# MIDI_connector.net
KiCad netlist of a schematic drawn in Altium Designer
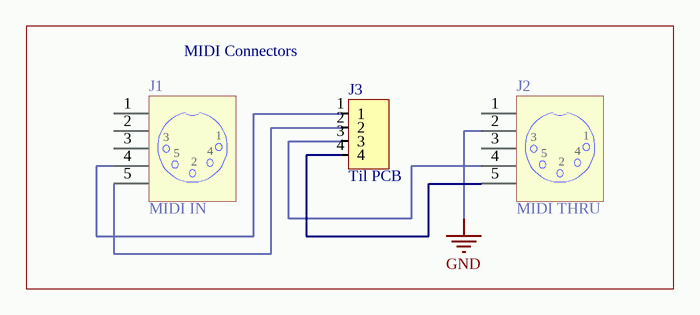
[diagram p0: MIDI_connector.SchDoc]

(export (version "E")
  (design (tool "Eeschema 10.0.6"))
  (components
    (comp (ref "J1")
      (value "MIDI IN")
      (footprint "KONV-KMFCDIN76005_V")
      (description "Socket, 5-way R/A DIN")
      (fields (field (name "MANUFACTURER") "Konvee Electronic") (field (name "PARTNUMBER") "KMFCDIN76005"))
      (libsource (lib "Altium Content Vault") (part "CMP-0406-00001-1"))
    )
    (comp (ref "J2")
      (value "MIDI THRU")
      (footprint "KONV-KMFCDIN76005_V")
      (description "Socket, 5-way R/A DIN")
      (fields (field (name "MANUFACTURER") "Konvee Electronic") (field (name "PARTNUMBER") "KMFCDIN76005"))
      (libsource (lib "Altium Content Vault") (part "CMP-0406-00001-1"))
    )
    (comp (ref "J3") (value "Til PCB") (footprint "JST 4pin") (libsource (lib "Schlib1") (part "JST 4pin")))
  )
  (nets
    (net (code "1") (name "GND") (class "Default")
      (node (ref "J2") (pin "2") (pinfunction "2_2") (pintype "passive"))
    )
    (net (code "2") (name "Net-(J1-Pad4)") (class "Default")
      (node (ref "J1") (pin "4") (pinfunction "4_4") (pintype "passive"))
      (node (ref "J3") (pin "1") (pinfunction "1_1") (pintype "passive"))
    )
    (net (code "3") (name "Net-(J1-Pad5)") (class "Default")
      (node (ref "J1") (pin "5") (pinfunction "5_5") (pintype "passive"))
      (node (ref "J3") (pin "2") (pinfunction "2_2") (pintype "passive"))
    )
    (net (code "4") (name "Net-(J2-Pad4)") (class "Default")
      (node (ref "J2") (pin "4") (pinfunction "4_4") (pintype "passive"))
      (node (ref "J3") (pin "3") (pinfunction "3_3") (pintype "passive"))
    )
    (net (code "5") (name "Net-(J2-Pad5)") (class "Default")
      (node (ref "J2") (pin "5") (pinfunction "5_5") (pintype "passive"))
      (node (ref "J3") (pin "4") (pinfunction "4_4") (pintype "passive"))
    )
    (net (code "6") (name "unconnected-(J1-Pad1)") (class "Default")
      (node (ref "J1") (pin "1") (pinfunction "1_1") (pintype "passive"))
    )
    (net (code "7") (name "unconnected-(J1-Pad2)") (class "Default")
      (node (ref "J1") (pin "2") (pinfunction "2_2") (pintype "passive"))
    )
    (net (code "8") (name "unconnected-(J1-Pad3)") (class "Default")
      (node (ref "J1") (pin "3") (pinfunction "3_3") (pintype "passive"))
    )
    (net (code "9") (name "unconnected-(J1-PadMH1)") (class "Default")
      (node (ref "J1") (pin "MH1") (pinfunction "MH1_MH1") (pintype "passive"))
    )
    (net (code "10") (name "unconnected-(J1-PadMH2)") (class "Default")
      (node (ref "J1") (pin "MH2") (pinfunction "MH2_MH2") (pintype "passive"))
    )
    (net (code "11") (name "unconnected-(J2-Pad1)") (class "Default")
      (node (ref "J2") (pin "1") (pinfunction "1_1") (pintype "passive"))
    )
    (net (code "12") (name "unconnected-(J2-Pad3)") (class "Default")
      (node (ref "J2") (pin "3") (pinfunction "3_3") (pintype "passive"))
    )
    (net (code "13") (name "unconnected-(J2-PadMH1)") (class "Default")
      (node (ref "J2") (pin "MH1") (pinfunction "MH1_MH1") (pintype "passive"))
    )
    (net (code "14") (name "unconnected-(J2-PadMH2)") (class "Default")
      (node (ref "J2") (pin "MH2") (pinfunction "MH2_MH2") (pintype "passive"))
    )
  )
)
